# main.net
KiCad netlist of a schematic drawn in Altium Designer
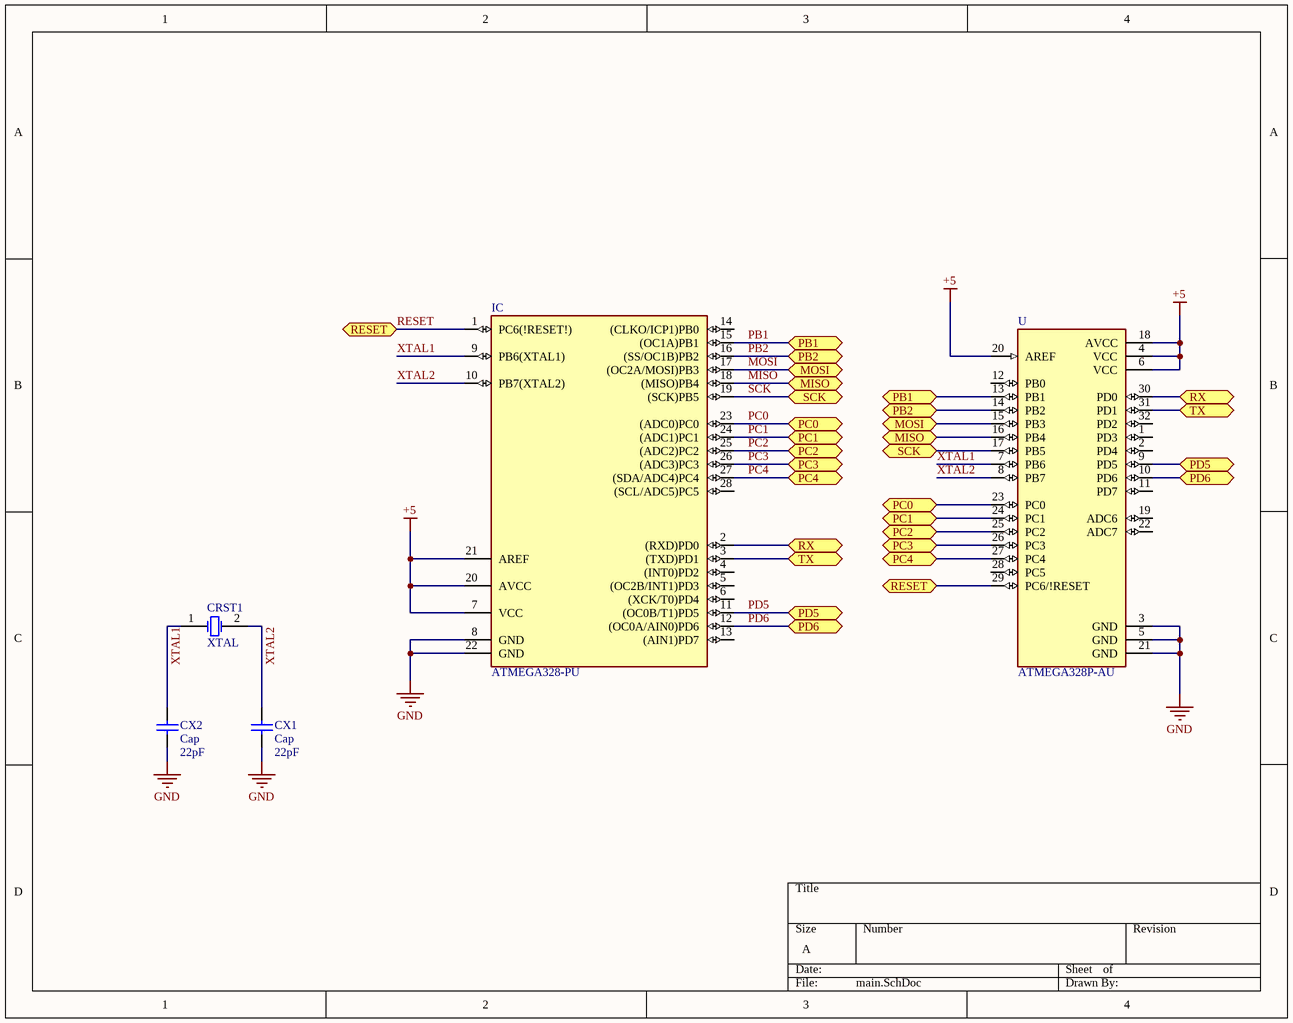
[diagram p0: main.SchDoc]

(export (version "E")
  (design (tool "Eeschema 10.0.6"))
  (components
    (comp (ref "CRST1")
      (value "XTAL")
      (footprint "R38")
      (description "Crystal Oscillator")
      (fields (field (name "PUBLISHER") "Altium Limited"))
      (libsource (lib "Miscellaneous Devices") (part "XTAL"))
    )
    (comp (ref "CX1")
      (value "Cap")
      (footprint "RAD-0.3")
      (description "Capacitor")
      (fields (field (name "ALTIUM_VALUE") "22pF") (field (name "PUBLISHER") "Altium Limited"))
      (libsource (lib "Miscellaneous Devices") (part "Cap"))
    )
    (comp (ref "CX2")
      (value "Cap")
      (footprint "RAD-0.3")
      (description "Capacitor")
      (fields (field (name "ALTIUM_VALUE") "22pF") (field (name "PUBLISHER") "Altium Limited"))
      (libsource (lib "Miscellaneous Devices") (part "Cap"))
    )
    (comp (ref "IC")
      (value "ATMEGA328-PU")
      (footprint "DIL28")
      (description "AVR AVRÂ® ATmega Microcontroller IC 8-Bit 20MHz 32KB _16K x 16_ FLASH 28-PDIP")
      (fields (field (name "MF") "Microchip Technology"))
      (libsource (lib "ATMEGA328P-DIP") (part "ATMEGA328-PU"))
    )
    (comp (ref "U")
      (value "ATMEGA328P-AU")
      (footprint "QFP80P900X900X120-32N")
      (description "AVR AVRÂ® ATmega Microcontroller IC 8-Bit 20MHz 32KB _16K x 16_ FLASH 32-TQFP _7x7_")
      (fields (field (name "MF") "Microchip"))
      (libsource (lib "atmega328p") (part "ATMEGA328P-AU"))
    )
  )
  (nets
    (net (code "1") (name "+5") (class "Default")
      (node (ref "IC") (pin "20") (pinfunction "AVCC_20") (pintype "power_in"))
      (node (ref "IC") (pin "21") (pinfunction "AREF_21") (pintype "passive"))
      (node (ref "IC") (pin "7") (pinfunction "VCC_7") (pintype "power_in"))
      (node (ref "U") (pin "18") (pinfunction "AVCC_18") (pintype "power_in"))
      (node (ref "U") (pin "20") (pinfunction "AREF_20") (pintype "input"))
      (node (ref "U") (pin "4") (pinfunction "VCC_4") (pintype "power_in"))
      (node (ref "U") (pin "6") (pinfunction "VCC_6") (pintype "power_in"))
    )
    (net (code "2") (name "/MISO") (class "Default")
      (node (ref "IC") (pin "18") (pinfunction "(MISO)PB4_18") (pintype "bidirectional"))
      (node (ref "U") (pin "16") (pinfunction "PB4_16") (pintype "bidirectional"))
    )
    (net (code "3") (name "/MOSI") (class "Default")
      (node (ref "IC") (pin "17") (pinfunction "(OC2A/MOSI)PB3_17") (pintype "bidirectional"))
      (node (ref "U") (pin "15") (pinfunction "PB3_15") (pintype "bidirectional"))
    )
    (net (code "4") (name "/PB1") (class "Default")
      (node (ref "IC") (pin "15") (pinfunction "(OC1A)PB1_15") (pintype "bidirectional"))
      (node (ref "U") (pin "13") (pinfunction "PB1_13") (pintype "bidirectional"))
    )
    (net (code "5") (name "/PB2") (class "Default")
      (node (ref "IC") (pin "16") (pinfunction "(SS/OC1B)PB2_16") (pintype "bidirectional"))
      (node (ref "U") (pin "14") (pinfunction "PB2_14") (pintype "bidirectional"))
    )
    (net (code "6") (name "/PC0") (class "Default")
      (node (ref "IC") (pin "23") (pinfunction "(ADC0)PC0_23") (pintype "bidirectional"))
      (node (ref "U") (pin "23") (pinfunction "PC0_23") (pintype "bidirectional"))
    )
    (net (code "7") (name "/PC1") (class "Default")
      (node (ref "IC") (pin "24") (pinfunction "(ADC1)PC1_24") (pintype "bidirectional"))
      (node (ref "U") (pin "24") (pinfunction "PC1_24") (pintype "bidirectional"))
    )
    (net (code "8") (name "/PC2") (class "Default")
      (node (ref "IC") (pin "25") (pinfunction "(ADC2)PC2_25") (pintype "bidirectional"))
      (node (ref "U") (pin "25") (pinfunction "PC2_25") (pintype "bidirectional"))
    )
    (net (code "9") (name "/PC3") (class "Default")
      (node (ref "IC") (pin "26") (pinfunction "(ADC3)PC3_26") (pintype "bidirectional"))
      (node (ref "U") (pin "26") (pinfunction "PC3_26") (pintype "bidirectional"))
    )
    (net (code "10") (name "/PC4") (class "Default")
      (node (ref "IC") (pin "27") (pinfunction "(SDA/ADC4)PC4_27") (pintype "bidirectional"))
      (node (ref "U") (pin "27") (pinfunction "PC4_27") (pintype "bidirectional"))
    )
    (net (code "11") (name "/PD5") (class "Default")
      (node (ref "IC") (pin "11") (pinfunction "(OC0B/T1)PD5_11") (pintype "bidirectional"))
      (node (ref "U") (pin "9") (pinfunction "PD5_9") (pintype "bidirectional"))
    )
    (net (code "12") (name "/PD6") (class "Default")
      (node (ref "IC") (pin "12") (pinfunction "(OC0A/AIN0)PD6_12") (pintype "bidirectional"))
      (node (ref "U") (pin "10") (pinfunction "PD6_10") (pintype "bidirectional"))
    )
    (net (code "13") (name "/RESET") (class "Default")
      (node (ref "IC") (pin "1") (pinfunction "PC6(!RESET!)_1") (pintype "bidirectional"))
      (node (ref "U") (pin "29") (pinfunction "PC6/!RESET_29") (pintype "bidirectional"))
    )
    (net (code "14") (name "/RX") (class "Default")
      (node (ref "IC") (pin "2") (pinfunction "(RXD)PD0_2") (pintype "bidirectional"))
      (node (ref "U") (pin "30") (pinfunction "PD0_30") (pintype "bidirectional"))
    )
    (net (code "15") (name "/SCK") (class "Default")
      (node (ref "IC") (pin "19") (pinfunction "(SCK)PB5_19") (pintype "bidirectional"))
      (node (ref "U") (pin "17") (pinfunction "PB5_17") (pintype "bidirectional"))
    )
    (net (code "16") (name "/TX") (class "Default")
      (node (ref "IC") (pin "3") (pinfunction "(TXD)PD1_3") (pintype "bidirectional"))
      (node (ref "U") (pin "31") (pinfunction "PD1_31") (pintype "bidirectional"))
    )
    (net (code "17") (name "/XTAL1") (class "Default")
      (node (ref "CRST1") (pin "1") (pinfunction "OSC1_1") (pintype "passive"))
      (node (ref "CX2") (pin "1") (pinfunction "1_1") (pintype "passive"))
      (node (ref "IC") (pin "9") (pinfunction "PB6(XTAL1)_9") (pintype "bidirectional"))
      (node (ref "U") (pin "7") (pinfunction "PB6_7") (pintype "bidirectional"))
    )
    (net (code "18") (name "/XTAL2") (class "Default")
      (node (ref "CRST1") (pin "2") (pinfunction "OSC2_2") (pintype "passive"))
      (node (ref "CX1") (pin "1") (pinfunction "1_1") (pintype "passive"))
      (node (ref "IC") (pin "10") (pinfunction "PB7(XTAL2)_10") (pintype "bidirectional"))
      (node (ref "U") (pin "8") (pinfunction "PB7_8") (pintype "bidirectional"))
    )
    (net (code "19") (name "GND") (class "Default")
      (node (ref "CX1") (pin "2") (pinfunction "2_2") (pintype "passive"))
      (node (ref "CX2") (pin "2") (pinfunction "2_2") (pintype "passive"))
      (node (ref "IC") (pin "22") (pinfunction "GND_22") (pintype "power_in"))
      (node (ref "IC") (pin "8") (pinfunction "GND_8") (pintype "power_in"))
      (node (ref "U") (pin "21") (pinfunction "GND_21") (pintype "power_in"))
      (node (ref "U") (pin "3") (pinfunction "GND_3") (pintype "power_in"))
      (node (ref "U") (pin "5") (pinfunction "GND_5") (pintype "power_in"))
    )
    (net (code "20") (name "unconnected-(IC-(AIN1)PD7-Pad13)") (class "Default")
      (node (ref "IC") (pin "13") (pinfunction "(AIN1)PD7_13") (pintype "bidirectional"))
    )
    (net (code "21") (name "unconnected-(IC-(CLKO{slash}ICP1)PB0-Pad14)") (class "Default")
      (node (ref "IC") (pin "14") (pinfunction "(CLKO/ICP1)PB0_14") (pintype "bidirectional"))
    )
    (net (code "22") (name "unconnected-(IC-(INT0)PD2-Pad4)") (class "Default")
      (node (ref "IC") (pin "4") (pinfunction "(INT0)PD2_4") (pintype "bidirectional"))
    )
    (net (code "23") (name "unconnected-(IC-(OC2B{slash}INT1)PD3-Pad5)") (class "Default")
      (node (ref "IC") (pin "5") (pinfunction "(OC2B/INT1)PD3_5") (pintype "bidirectional"))
    )
    (net (code "24") (name "unconnected-(IC-(SCL{slash}ADC5)PC5-Pad28)") (class "Default")
      (node (ref "IC") (pin "28") (pinfunction "(SCL/ADC5)PC5_28") (pintype "bidirectional"))
    )
    (net (code "25") (name "unconnected-(IC-(XCK{slash}T0)PD4-Pad6)") (class "Default")
      (node (ref "IC") (pin "6") (pinfunction "(XCK/T0)PD4_6") (pintype "bidirectional"))
    )
    (net (code "26") (name "unconnected-(U-ADC6-Pad19)") (class "Default")
      (node (ref "U") (pin "19") (pinfunction "ADC6_19") (pintype "bidirectional"))
    )
    (net (code "27") (name "unconnected-(U-ADC7-Pad22)") (class "Default")
      (node (ref "U") (pin "22") (pinfunction "ADC7_22") (pintype "bidirectional"))
    )
    (net (code "28") (name "unconnected-(U-PB0-Pad12)") (class "Default")
      (node (ref "U") (pin "12") (pinfunction "PB0_12") (pintype "bidirectional"))
    )
    (net (code "29") (name "unconnected-(U-PC5-Pad28)") (class "Default")
      (node (ref "U") (pin "28") (pinfunction "PC5_28") (pintype "bidirectional"))
    )
    (net (code "30") (name "unconnected-(U-PD2-Pad32)") (class "Default")
      (node (ref "U") (pin "32") (pinfunction "PD2_32") (pintype "bidirectional"))
    )
    (net (code "31") (name "unconnected-(U-PD3-Pad1)") (class "Default")
      (node (ref "U") (pin "1") (pinfunction "PD3_1") (pintype "bidirectional"))
    )
    (net (code "32") (name "unconnected-(U-PD4-Pad2)") (class "Default")
      (node (ref "U") (pin "2") (pinfunction "PD4_2") (pintype "bidirectional"))
    )
    (net (code "33") (name "unconnected-(U-PD7-Pad11)") (class "Default")
      (node (ref "U") (pin "11") (pinfunction "PD7_11") (pintype "bidirectional"))
    )
  )
)
